# USBHostShield-Rev2.net
KiCad netlist of a schematic drawn in EAGLE
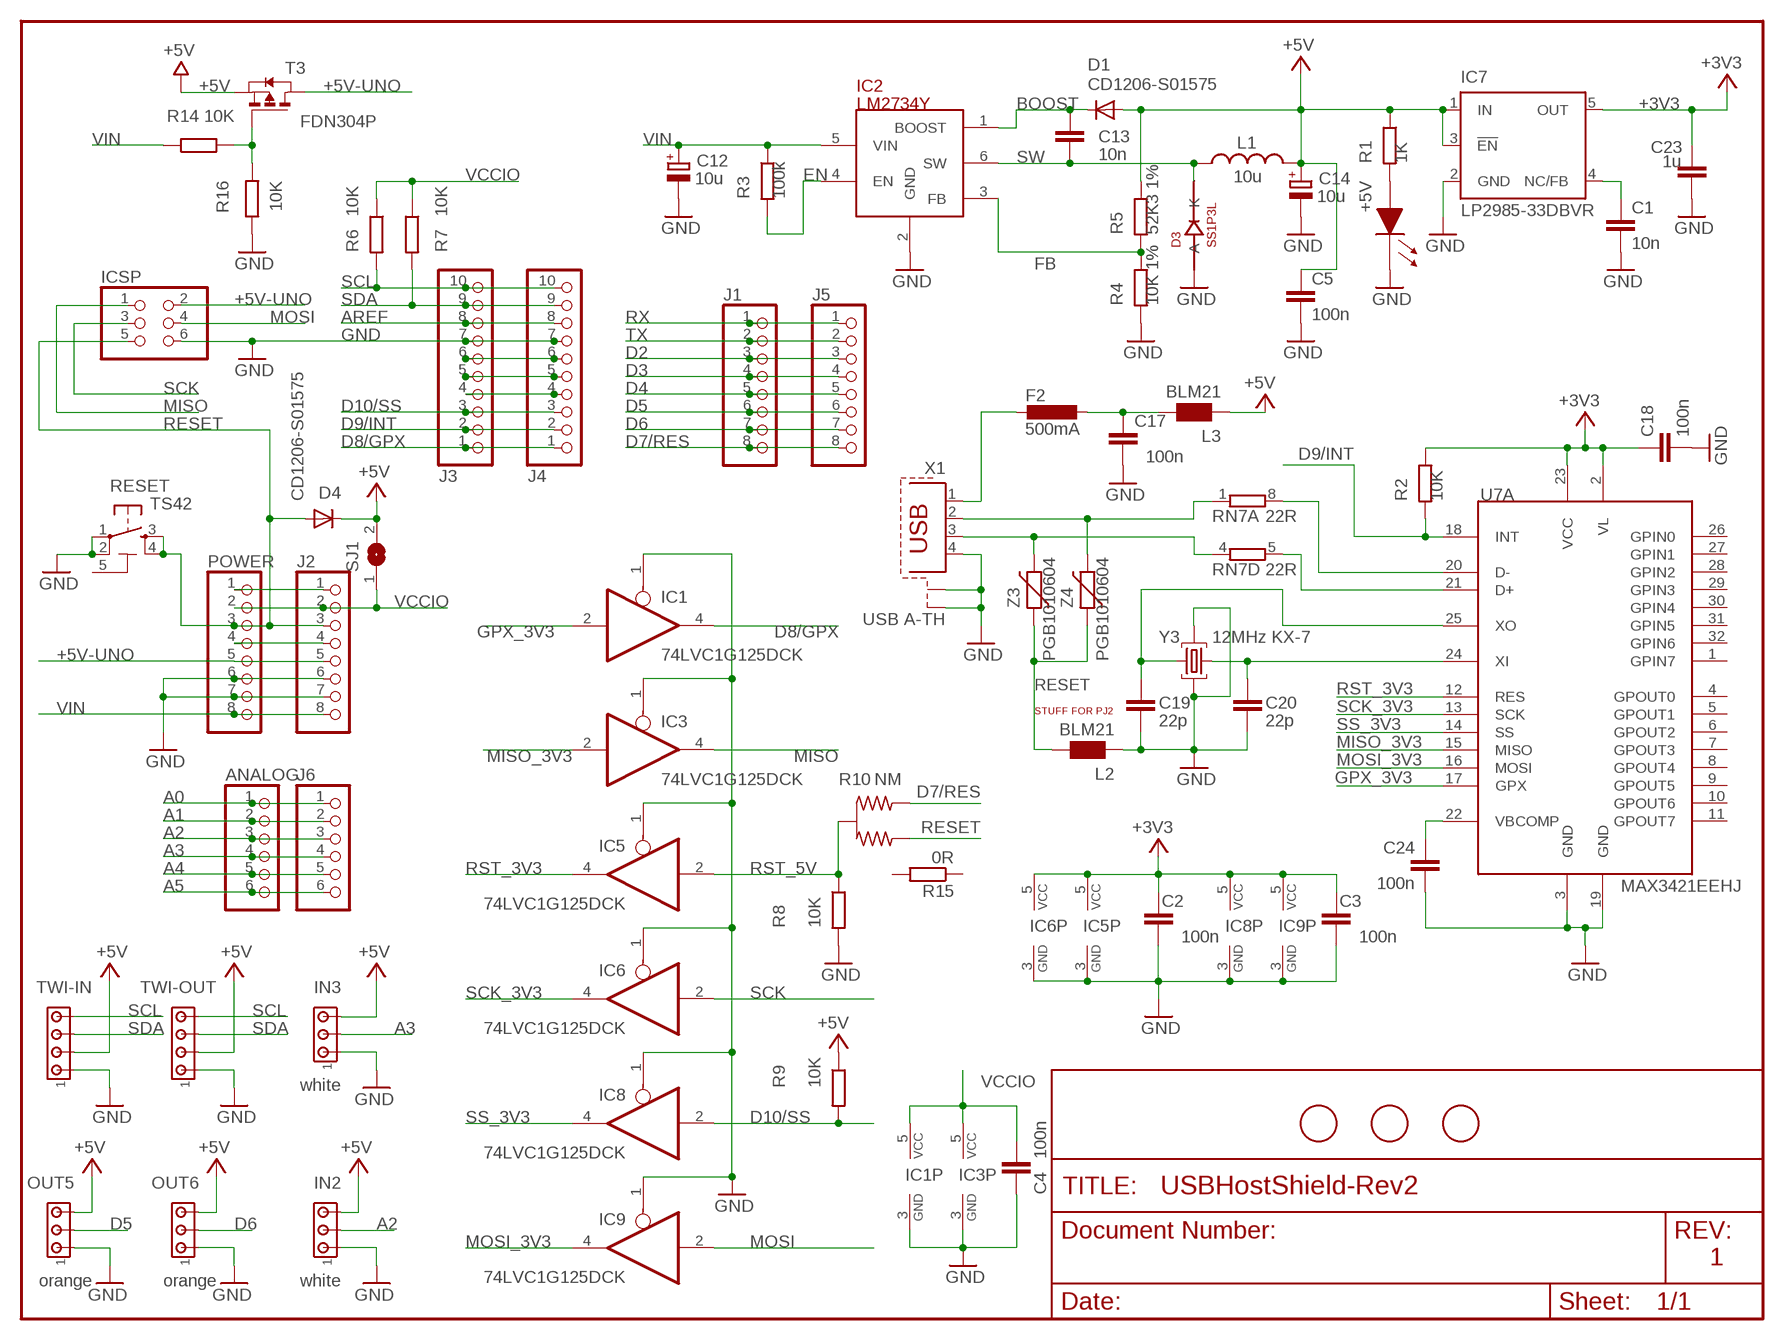
[diagram p0: schematic, sheet 1]

(export (version "E")
  (design (tool "Eeschema 10.0.6"))
  (components
    (comp (ref "+5V")
      (value "MYSMD_LED0805")
      (footprint "eagle-import:SMD_LED0805")
      (libsource (lib "eagle-import") (part "MYSMD_LED0805"))
    )
    (comp (ref "ANALOG")
      (value "PINHD-1X6TH")
      (footprint "eagle-import:1X06-TH")
      (libsource (lib "eagle-import") (part "PINHD-1X6TH"))
    )
    (comp (ref "C1")
      (value "10n")
      (footprint "eagle-import:C0603-ROUND")
      (libsource (lib "eagle-import") (part "C-EUC0603"))
    )
    (comp (ref "C2")
      (value "100n")
      (footprint "eagle-import:C0603-ROUND")
      (libsource (lib "eagle-import") (part "C-EU0603-RND"))
    )
    (comp (ref "C3")
      (value "100n")
      (footprint "eagle-import:C0603-ROUND")
      (libsource (lib "eagle-import") (part "C-EU0603-RND"))
    )
    (comp (ref "C4")
      (value "100n")
      (footprint "eagle-import:C0603-ROUND")
      (libsource (lib "eagle-import") (part "C-EU0603-RND"))
    )
    (comp (ref "C5")
      (value "100n")
      (footprint "eagle-import:C0603-ROUND")
      (libsource (lib "eagle-import") (part "C-EU0603-RND"))
    )
    (comp (ref "C12")
      (value "10u")
      (footprint "eagle-import:SMC_B")
      (libsource (lib "eagle-import") (part "CPOL-EUSMCB"))
    )
    (comp (ref "C13")
      (value "10n")
      (footprint "eagle-import:C0603-ROUND")
      (libsource (lib "eagle-import") (part "C-EUC0603"))
    )
    (comp (ref "C14")
      (value "10u")
      (footprint "eagle-import:SMC_B")
      (libsource (lib "eagle-import") (part "CPOL-EUSMCB"))
    )
    (comp (ref "C17")
      (value "100n")
      (footprint "eagle-import:C0603-ROUND")
      (libsource (lib "eagle-import") (part "C-EU0603-RND"))
    )
    (comp (ref "C18")
      (value "100n")
      (footprint "eagle-import:C0603-ROUND")
      (libsource (lib "eagle-import") (part "C-EU0603-RND"))
    )
    (comp (ref "C19")
      (value "22p")
      (footprint "eagle-import:C0603-ROUND")
      (libsource (lib "eagle-import") (part "C-EU0603-RND"))
    )
    (comp (ref "C20")
      (value "22p")
      (footprint "eagle-import:C0603-ROUND")
      (libsource (lib "eagle-import") (part "C-EU0603-RND"))
    )
    (comp (ref "C23")
      (value "1u")
      (footprint "eagle-import:C0603-ROUND")
      (libsource (lib "eagle-import") (part "C-EU0603-RND"))
    )
    (comp (ref "C24")
      (value "100n")
      (footprint "eagle-import:C0603-ROUND")
      (libsource (lib "eagle-import") (part "C-EU0603-RND"))
    )
    (comp (ref "D1")
      (value "CD1206-S01575")
      (footprint "eagle-import:MINIMELF")
      (libsource (lib "eagle-import") (part "DIODE-MINIMELF"))
    )
    (comp (ref "D3")
      (value "SS1P3L")
      (footprint "eagle-import:DO220AAL")
      (libsource (lib "eagle-import") (part "SS1P3L"))
    )
    (comp (ref "D4")
      (value "CD1206-S01575")
      (footprint "eagle-import:MINIMELF")
      (libsource (lib "eagle-import") (part "DIODE-MINIMELF"))
    )
    (comp (ref "F2")
      (value "500mA")
      (footprint "eagle-import:L1812")
      (libsource (lib "eagle-import") (part "L-EUL1812"))
    )
    (comp (ref "IC1")
      (value "74LVC1G125DCK")
      (footprint "eagle-import:SC70-5")
      (libsource (lib "eagle-import") (part "741G125DCKLVC"))
    )
    (comp (ref "IC2")
      (value "LM2734Y")
      (footprint "eagle-import:SOT23-6")
      (libsource (lib "eagle-import") (part "LM2736Y"))
    )
    (comp (ref "IC3")
      (value "74LVC1G125DCK")
      (footprint "eagle-import:SC70-5")
      (libsource (lib "eagle-import") (part "741G125DCKLVC"))
    )
    (comp (ref "IC5")
      (value "74LVC1G125DCK")
      (footprint "eagle-import:SC70-5")
      (libsource (lib "eagle-import") (part "741G125DCKLVC"))
    )
    (comp (ref "IC6")
      (value "74LVC1G125DCK")
      (footprint "eagle-import:SC70-5")
      (libsource (lib "eagle-import") (part "741G125DCKLVC"))
    )
    (comp (ref "IC7")
      (value "LP2985-33DBVR")
      (footprint "eagle-import:SOT23-DBV")
      (libsource (lib "eagle-import") (part "TPS77033"))
    )
    (comp (ref "IC8")
      (value "74LVC1G125DCK")
      (footprint "eagle-import:SC70-5")
      (libsource (lib "eagle-import") (part "741G125DCKLVC"))
    )
    (comp (ref "IC9")
      (value "74LVC1G125DCK")
      (footprint "eagle-import:SC70-5")
      (libsource (lib "eagle-import") (part "741G125DCKLVC"))
    )
    (comp (ref "ICSP")
      (value "PINHD-2X3")
      (footprint "eagle-import:2X03")
      (libsource (lib "eagle-import") (part "PINHD-2X3"))
    )
    (comp (ref "IN2")
      (value "white")
      (footprint "eagle-import:10X03MTA")
      (fields (field (name "PART_NUMBER") "LHA-03-TS"))
      (libsource (lib "eagle-import") (part "0141_LHA-03-TS"))
    )
    (comp (ref "IN3")
      (value "white")
      (footprint "eagle-import:10X03MTA")
      (fields (field (name "PART_NUMBER") "LHA-03-TS"))
      (libsource (lib "eagle-import") (part "0141_LHA-03-TS"))
    )
    (comp (ref "J1")
      (value "PINHD-1X8TH")
      (footprint "eagle-import:1X08-TH")
      (libsource (lib "eagle-import") (part "PINHD-1X8TH"))
    )
    (comp (ref "J2")
      (value "PINHD-1X8TH")
      (footprint "eagle-import:1X08-TH")
      (libsource (lib "eagle-import") (part "PINHD-1X8TH"))
    )
    (comp (ref "J3")
      (value "PINHD-1X10TH")
      (footprint "eagle-import:1X10-TH")
      (libsource (lib "eagle-import") (part "PINHD-1X10TH"))
    )
    (comp (ref "J4")
      (value "PINHD-1X10TH")
      (footprint "eagle-import:1X10-TH")
      (libsource (lib "eagle-import") (part "PINHD-1X10TH"))
    )
    (comp (ref "J5")
      (value "PINHD-1X8TH")
      (footprint "eagle-import:1X08-TH")
      (libsource (lib "eagle-import") (part "PINHD-1X8TH"))
    )
    (comp (ref "J6")
      (value "PINHD-1X6TH")
      (footprint "eagle-import:1X06-TH")
      (libsource (lib "eagle-import") (part "PINHD-1X6TH"))
    )
    (comp (ref "L1")
      (value "10u")
      (footprint "eagle-import:SRR0604")
      (libsource (lib "eagle-import") (part "L-USSRR0604"))
    )
    (comp (ref "L2")
      (value "BLM21")
      (footprint "eagle-import:0805")
      (libsource (lib "eagle-import") (part "WE-CBF_0805"))
    )
    (comp (ref "L3")
      (value "BLM21")
      (footprint "eagle-import:0805")
      (libsource (lib "eagle-import") (part "WE-CBF_0805"))
    )
    (comp (ref "OUT5")
      (value "orange")
      (footprint "eagle-import:10X03MTA")
      (fields (field (name "PART_NUMBER") "LHA-03-TS-P1585C"))
      (libsource (lib "eagle-import") (part "0481_LHA-03-TS-P1585C"))
    )
    (comp (ref "OUT6")
      (value "orange")
      (footprint "eagle-import:10X03MTA")
      (fields (field (name "PART_NUMBER") "LHA-03-TS-P1585C"))
      (libsource (lib "eagle-import") (part "0481_LHA-03-TS-P1585C"))
    )
    (comp (ref "POWER")
      (value "PINHD-1X8TH")
      (footprint "eagle-import:1X08-TH")
      (libsource (lib "eagle-import") (part "PINHD-1X8TH"))
    )
    (comp (ref "R1")
      (value "1K")
      (footprint "eagle-import:R0603-ROUND")
      (libsource (lib "eagle-import") (part "R-EU_0603-RND"))
    )
    (comp (ref "R2")
      (value "10K")
      (footprint "eagle-import:R0603-ROUND")
      (libsource (lib "eagle-import") (part "R-EU_0603-RND"))
    )
    (comp (ref "R3")
      (value "100k")
      (footprint "eagle-import:R0603-ROUND")
      (libsource (lib "eagle-import") (part "R-EU_0603-RND"))
    )
    (comp (ref "R4")
      (value "10K 1%")
      (footprint "eagle-import:R0603-ROUND")
      (libsource (lib "eagle-import") (part "R-EU_0603-RND"))
    )
    (comp (ref "R5")
      (value "52K3 1%")
      (footprint "eagle-import:R0603-ROUND")
      (libsource (lib "eagle-import") (part "R-EU_0603-RND"))
    )
    (comp (ref "R6")
      (value "10K")
      (footprint "eagle-import:R0603-ROUND")
      (libsource (lib "eagle-import") (part "R-EU_0603-RND"))
    )
    (comp (ref "R7")
      (value "10K")
      (footprint "eagle-import:R0603-ROUND")
      (libsource (lib "eagle-import") (part "R-EU_0603-RND"))
    )
    (comp (ref "R8")
      (value "10K")
      (footprint "eagle-import:R0603-ROUND")
      (libsource (lib "eagle-import") (part "R-EU_0603-RND"))
    )
    (comp (ref "R9")
      (value "10K")
      (footprint "eagle-import:R0603-ROUND")
      (libsource (lib "eagle-import") (part "R-EU_0603-RND"))
    )
    (comp (ref "R10")
      (value "NM")
      (footprint "eagle-import:J0402")
      (libsource (lib "eagle-import") (part "J0402"))
    )
    (comp (ref "R14")
      (value "10K")
      (footprint "eagle-import:R0603-ROUND")
      (libsource (lib "eagle-import") (part "R-EU_0603-RND"))
    )
    (comp (ref "R15")
      (value "0R")
      (footprint "eagle-import:R0402")
      (libsource (lib "eagle-import") (part "R-EU_R0402"))
    )
    (comp (ref "R16")
      (value "10K")
      (footprint "eagle-import:R0603-ROUND")
      (libsource (lib "eagle-import") (part "R-EU_0603-RND"))
    )
    (comp (ref "RESET")
      (value "TS42")
      (footprint "eagle-import:TS42")
      (libsource (lib "eagle-import") (part "TS42"))
    )
    (comp (ref "RN7")
      (value "22R")
      (footprint "eagle-import:CAY16")
      (libsource (lib "eagle-import") (part "4R-NCAY16"))
    )
    (comp (ref "SJ1") (value "SJ") (footprint "eagle-import:SJ") (libsource (lib "eagle-import") (part "SJ")))
    (comp (ref "T3")
      (value "FDN304P")
      (footprint "eagle-import:SOT-23")
      (libsource (lib "eagle-import") (part "PMOSSOT23"))
    )
    (comp (ref "TWI-IN")
      (value "0205_LHA-04-TS__4X1_VERTICALE_BIANCO_P_2,54")
      (footprint "eagle-import:10X04MTA")
      (fields (field (name "PART_NUMBER") "LHA-04-TS__4x1_Verticale_Bianco_p_2,54"))
      (libsource (lib "eagle-import") (part "0205_LHA-04-TS__4X1_VERTICALE_BIANCO_P_2,54"))
    )
    (comp (ref "TWI-OUT")
      (value "0205_LHA-04-TS__4X1_VERTICALE_BIANCO_P_2,54")
      (footprint "eagle-import:10X04MTA")
      (fields (field (name "PART_NUMBER") "LHA-04-TS__4x1_Verticale_Bianco_p_2,54"))
      (libsource (lib "eagle-import") (part "0205_LHA-04-TS__4X1_VERTICALE_BIANCO_P_2,54"))
    )
    (comp (ref "U$1")
      (value "FIDUCIALMOUNT")
      (footprint "eagle-import:FIDUCIA-MOUNT")
      (libsource (lib "eagle-import") (part "FIDUCIALMOUNT"))
    )
    (comp (ref "U$3")
      (value "FIDUCIALMOUNT")
      (footprint "eagle-import:FIDUCIA-MOUNT")
      (libsource (lib "eagle-import") (part "FIDUCIALMOUNT"))
    )
    (comp (ref "U$6")
      (value "FIDUCIALMOUNT")
      (footprint "eagle-import:FIDUCIA-MOUNT")
      (libsource (lib "eagle-import") (part "FIDUCIALMOUNT"))
    )
    (comp (ref "U7A")
      (value "MAX3421EEHJ")
      (footprint "eagle-import:TQFP32-05")
      (libsource (lib "eagle-import") (part "MAX3421EEHJ"))
    )
    (comp (ref "X1")
      (value "USB A-TH")
      (footprint "eagle-import:PN87520-S")
      (libsource (lib "eagle-import") (part "PN87520-S"))
    )
    (comp (ref "Y3")
      (value "12MHz KX-7")
      (footprint "eagle-import:CRYSTAL-3.2-2.5")
      (libsource (lib "eagle-import") (part "CRYSTAL-3.2-2.5"))
    )
    (comp (ref "Z3")
      (value "PGB1010604")
      (footprint "eagle-import:CT_CN0603")
      (libsource (lib "eagle-import") (part "VARISTORCN0603"))
    )
    (comp (ref "Z4")
      (value "PGB1010604")
      (footprint "eagle-import:CT_CN0603")
      (libsource (lib "eagle-import") (part "VARISTORCN0603"))
    )
  )
  (nets
    (net (code "1") (name "+3V3") (class "Default")
      (node (ref "C18") (pin "1") (pinfunction "1_1") (pintype "passive"))
      (node (ref "C2") (pin "1") (pinfunction "1_1") (pintype "passive"))
      (node (ref "C23") (pin "2") (pinfunction "2_2") (pintype "passive"))
      (node (ref "C3") (pin "1") (pinfunction "1_1") (pintype "passive"))
      (node (ref "IC5") (pin "5") (pinfunction "VCC_5") (pintype "power_in"))
      (node (ref "IC6") (pin "5") (pinfunction "VCC_5") (pintype "power_in"))
      (node (ref "IC7") (pin "5") (pinfunction "OUT_5") (pintype "passive"))
      (node (ref "IC8") (pin "5") (pinfunction "VCC_5") (pintype "power_in"))
      (node (ref "IC9") (pin "5") (pinfunction "VCC_5") (pintype "power_in"))
      (node (ref "R2") (pin "1") (pinfunction "1_1") (pintype "passive"))
      (node (ref "U7A") (pin "2") (pinfunction "VL_2") (pintype "bidirectional"))
      (node (ref "U7A") (pin "23") (pinfunction "VCC_23") (pintype "bidirectional"))
    )
    (net (code "2") (name "+5V") (class "Default")
      (node (ref "C14") (pin "+") (pinfunction "+_+") (pintype "passive"))
      (node (ref "C5") (pin "1") (pinfunction "1_1") (pintype "passive"))
      (node (ref "D1") (pin "A") (pinfunction "A_A") (pintype "passive"))
      (node (ref "D4") (pin "C") (pinfunction "C_C") (pintype "passive"))
      (node (ref "IC7") (pin "1") (pinfunction "IN_1") (pintype "input"))
      (node (ref "IC7") (pin "3") (pinfunction "~{EN}_3") (pintype "input"))
      (node (ref "IN2") (pin "3") (pinfunction "3_3") (pintype "passive"))
      (node (ref "IN3") (pin "3") (pinfunction "3_3") (pintype "passive"))
      (node (ref "L1") (pin "P$2") (pinfunction "2_P$2") (pintype "passive"))
      (node (ref "L3") (pin "1") (pinfunction "1_1") (pintype "passive"))
      (node (ref "OUT5") (pin "3") (pinfunction "3_3") (pintype "passive"))
      (node (ref "OUT6") (pin "3") (pinfunction "3_3") (pintype "passive"))
      (node (ref "R1") (pin "1") (pinfunction "1_1") (pintype "passive"))
      (node (ref "R5") (pin "1") (pinfunction "1_1") (pintype "passive"))
      (node (ref "R9") (pin "1") (pinfunction "1_1") (pintype "passive"))
      (node (ref "SJ1") (pin "2") (pinfunction "2_2") (pintype "passive"))
      (node (ref "T3") (pin "2") (pinfunction "S_2") (pintype "passive"))
      (node (ref "TWI-IN") (pin "2") (pinfunction "2_2") (pintype "passive"))
      (node (ref "TWI-OUT") (pin "2") (pinfunction "2_2") (pintype "passive"))
    )
    (net (code "3") (name "/+5V-UNO") (class "Default")
      (node (ref "ICSP") (pin "2") (pinfunction "2_2") (pintype "passive"))
      (node (ref "J2") (pin "5") (pinfunction "5_5") (pintype "passive"))
      (node (ref "POWER") (pin "5") (pinfunction "5_5") (pintype "passive"))
      (node (ref "T3") (pin "1") (pinfunction "D_1") (pintype "passive"))
    )
    (net (code "4") (name "/5-GND") (class "Default")
      (node (ref "RESET") (pin "5") (pinfunction "5-GND_5") (pintype "power_in"))
    )
    (net (code "5") (name "/A0") (class "Default")
      (node (ref "ANALOG") (pin "1") (pinfunction "1_1") (pintype "passive"))
      (node (ref "J6") (pin "1") (pinfunction "1_1") (pintype "passive"))
    )
    (net (code "6") (name "/A1") (class "Default")
      (node (ref "ANALOG") (pin "2") (pinfunction "2_2") (pintype "passive"))
      (node (ref "J6") (pin "2") (pinfunction "2_2") (pintype "passive"))
    )
    (net (code "7") (name "/A2") (class "Default")
      (node (ref "ANALOG") (pin "3") (pinfunction "3_3") (pintype "passive"))
      (node (ref "IN2") (pin "2") (pinfunction "2_2") (pintype "passive"))
      (node (ref "J6") (pin "3") (pinfunction "3_3") (pintype "passive"))
    )
    (net (code "8") (name "/A3") (class "Default")
      (node (ref "ANALOG") (pin "4") (pinfunction "4_4") (pintype "passive"))
      (node (ref "IN3") (pin "2") (pinfunction "2_2") (pintype "passive"))
      (node (ref "J6") (pin "4") (pinfunction "4_4") (pintype "passive"))
    )
    (net (code "9") (name "/A4") (class "Default")
      (node (ref "ANALOG") (pin "5") (pinfunction "5_5") (pintype "passive"))
      (node (ref "J6") (pin "5") (pinfunction "5_5") (pintype "passive"))
    )
    (net (code "10") (name "/A5") (class "Default")
      (node (ref "ANALOG") (pin "6") (pinfunction "6_6") (pintype "passive"))
      (node (ref "J6") (pin "6") (pinfunction "6_6") (pintype "passive"))
    )
    (net (code "11") (name "/AREF") (class "Default")
      (node (ref "J3") (pin "8") (pinfunction "8_8") (pintype "passive"))
      (node (ref "J4") (pin "8") (pinfunction "8_8") (pintype "passive"))
    )
    (net (code "12") (name "/BOOST") (class "Default")
      (node (ref "C13") (pin "1") (pinfunction "1_1") (pintype "passive"))
      (node (ref "D1") (pin "C") (pinfunction "C_C") (pintype "passive"))
      (node (ref "IC2") (pin "1") (pinfunction "BOOST_1") (pintype "input"))
    )
    (net (code "13") (name "/D2") (class "Default")
      (node (ref "J1") (pin "3") (pinfunction "3_3") (pintype "passive"))
      (node (ref "J5") (pin "3") (pinfunction "3_3") (pintype "passive"))
    )
    (net (code "14") (name "/D3") (class "Default")
      (node (ref "J1") (pin "4") (pinfunction "4_4") (pintype "passive"))
      (node (ref "J5") (pin "4") (pinfunction "4_4") (pintype "passive"))
    )
    (net (code "15") (name "/D4") (class "Default")
      (node (ref "J1") (pin "5") (pinfunction "5_5") (pintype "passive"))
      (node (ref "J5") (pin "5") (pinfunction "5_5") (pintype "passive"))
    )
    (net (code "16") (name "/D5") (class "Default")
      (node (ref "J1") (pin "6") (pinfunction "6_6") (pintype "passive"))
      (node (ref "J5") (pin "6") (pinfunction "6_6") (pintype "passive"))
      (node (ref "OUT5") (pin "2") (pinfunction "2_2") (pintype "passive"))
    )
    (net (code "17") (name "/D6") (class "Default")
      (node (ref "J1") (pin "7") (pinfunction "7_7") (pintype "passive"))
      (node (ref "J5") (pin "7") (pinfunction "7_7") (pintype "passive"))
      (node (ref "OUT6") (pin "2") (pinfunction "2_2") (pintype "passive"))
    )
    (net (code "18") (name "/D7{slash}RES") (class "Default")
      (node (ref "J1") (pin "8") (pinfunction "8_8") (pintype "passive"))
      (node (ref "J5") (pin "8") (pinfunction "8_8") (pintype "passive"))
      (node (ref "R10") (pin "1") (pinfunction "1_1") (pintype "passive"))
    )
    (net (code "19") (name "/D8{slash}GPX") (class "Default")
      (node (ref "IC1") (pin "4") (pinfunction "O_4") (pintype "tri_state"))
      (node (ref "J3") (pin "1") (pinfunction "1_1") (pintype "passive"))
      (node (ref "J4") (pin "1") (pinfunction "1_1") (pintype "passive"))
    )
    (net (code "20") (name "/D9{slash}INT") (class "Default")
      (node (ref "J3") (pin "2") (pinfunction "2_2") (pintype "passive"))
      (node (ref "J4") (pin "2") (pinfunction "2_2") (pintype "passive"))
      (node (ref "R2") (pin "2") (pinfunction "2_2") (pintype "passive"))
      (node (ref "U7A") (pin "18") (pinfunction "INT_18") (pintype "bidirectional"))
    )
    (net (code "21") (name "/D10{slash}SS") (class "Default")
      (node (ref "IC8") (pin "2") (pinfunction "I_2") (pintype "input"))
      (node (ref "J3") (pin "3") (pinfunction "3_3") (pintype "passive"))
      (node (ref "J4") (pin "3") (pinfunction "3_3") (pintype "passive"))
      (node (ref "R9") (pin "2") (pinfunction "2_2") (pintype "passive"))
    )
    (net (code "22") (name "/EN") (class "Default")
      (node (ref "IC2") (pin "4") (pinfunction "EN_4") (pintype "input"))
      (node (ref "R3") (pin "2") (pinfunction "2_2") (pintype "passive"))
    )
    (net (code "23") (name "/FB") (class "Default")
      (node (ref "IC2") (pin "3") (pinfunction "FB_3") (pintype "input"))
      (node (ref "R4") (pin "1") (pinfunction "1_1") (pintype "passive"))
      (node (ref "R5") (pin "2") (pinfunction "2_2") (pintype "passive"))
    )
    (net (code "24") (name "/GPX_3V3") (class "Default")
      (node (ref "IC1") (pin "2") (pinfunction "I_2") (pintype "input"))
      (node (ref "U7A") (pin "17") (pinfunction "GPX_17") (pintype "bidirectional"))
    )
    (net (code "25") (name "/MISO") (class "Default")
      (node (ref "IC3") (pin "4") (pinfunction "O_4") (pintype "tri_state"))
      (node (ref "ICSP") (pin "1") (pinfunction "1_1") (pintype "passive"))
    )
    (net (code "26") (name "/MISO_3V3") (class "Default")
      (node (ref "IC3") (pin "2") (pinfunction "I_2") (pintype "input"))
      (node (ref "U7A") (pin "15") (pinfunction "MISO_15") (pintype "bidirectional"))
    )
    (net (code "27") (name "/MOSI") (class "Default")
      (node (ref "IC9") (pin "2") (pinfunction "I_2") (pintype "input"))
      (node (ref "ICSP") (pin "4") (pinfunction "4_4") (pintype "passive"))
    )
    (net (code "28") (name "/MOSI_3V3") (class "Default")
      (node (ref "IC9") (pin "4") (pinfunction "O_4") (pintype "tri_state"))
      (node (ref "U7A") (pin "16") (pinfunction "MOSI_16") (pintype "bidirectional"))
    )
    (net (code "29") (name "/RESET") (class "Default")
      (node (ref "D4") (pin "A") (pinfunction "A_A") (pintype "passive"))
      (node (ref "ICSP") (pin "5") (pinfunction "5_5") (pintype "passive"))
      (node (ref "J2") (pin "3") (pinfunction "3_3") (pintype "passive"))
      (node (ref "POWER") (pin "3") (pinfunction "3_3") (pintype "passive"))
      (node (ref "R10") (pin "3") (pinfunction "2_3") (pintype "passive"))
      (node (ref "RESET") (pin "3") (pinfunction "3_3") (pintype "passive"))
      (node (ref "RESET") (pin "4") (pinfunction "4_4") (pintype "passive"))
    )
    (net (code "30") (name "/RST_3V3") (class "Default")
      (node (ref "IC5") (pin "4") (pinfunction "O_4") (pintype "tri_state"))
      (node (ref "U7A") (pin "12") (pinfunction "RES_12") (pintype "bidirectional"))
    )
    (net (code "31") (name "/RST_5V") (class "Default")
      (node (ref "IC5") (pin "2") (pinfunction "I_2") (pintype "input"))
      (node (ref "R10") (pin "2") (pinfunction "C_2") (pintype "passive"))
      (node (ref "R8") (pin "1") (pinfunction "1_1") (pintype "passive"))
    )
    (net (code "32") (name "/RX") (class "Default")
      (node (ref "J1") (pin "1") (pinfunction "1_1") (pintype "passive"))
      (node (ref "J5") (pin "1") (pinfunction "1_1") (pintype "passive"))
    )
    (net (code "33") (name "/SCK") (class "Default")
      (node (ref "IC6") (pin "2") (pinfunction "I_2") (pintype "input"))
      (node (ref "ICSP") (pin "3") (pinfunction "3_3") (pintype "passive"))
    )
    (net (code "34") (name "/SCK_3V3") (class "Default")
      (node (ref "IC6") (pin "4") (pinfunction "O_4") (pintype "tri_state"))
      (node (ref "U7A") (pin "13") (pinfunction "SCK_13") (pintype "bidirectional"))
    )
    (net (code "35") (name "/SCL") (class "Default")
      (node (ref "J3") (pin "10") (pinfunction "10_10") (pintype "passive"))
      (node (ref "J4") (pin "10") (pinfunction "10_10") (pintype "passive"))
      (node (ref "R6") (pin "2") (pinfunction "2_2") (pintype "passive"))
      (node (ref "TWI-IN") (pin "4") (pinfunction "4_4") (pintype "passive"))
      (node (ref "TWI-OUT") (pin "4") (pinfunction "4_4") (pintype "passive"))
    )
    (net (code "36") (name "/SDA") (class "Default")
      (node (ref "J3") (pin "9") (pinfunction "9_9") (pintype "passive"))
      (node (ref "J4") (pin "9") (pinfunction "9_9") (pintype "passive"))
      (node (ref "R7") (pin "2") (pinfunction "2_2") (pintype "passive"))
      (node (ref "TWI-IN") (pin "3") (pinfunction "3_3") (pintype "passive"))
      (node (ref "TWI-OUT") (pin "3") (pinfunction "3_3") (pintype "passive"))
    )
    (net (code "37") (name "/SS_3V3") (class "Default")
      (node (ref "IC8") (pin "4") (pinfunction "O_4") (pintype "tri_state"))
      (node (ref "U7A") (pin "14") (pinfunction "SS_14") (pintype "bidirectional"))
    )
    (net (code "38") (name "/SW") (class "Default")
      (node (ref "C13") (pin "2") (pinfunction "2_2") (pintype "passive"))
      (node (ref "D3") (pin "P$1") (pinfunction "K_P$1") (pintype "bidirectional"))
      (node (ref "IC2") (pin "6") (pinfunction "SW_6") (pintype "output"))
      (node (ref "L1") (pin "P$1") (pinfunction "1_P$1") (pintype "passive"))
    )
    (net (code "39") (name "/TX") (class "Default")
      (node (ref "J1") (pin "2") (pinfunction "2_2") (pintype "passive"))
      (node (ref "J5") (pin "2") (pinfunction "2_2") (pintype "passive"))
    )
    (net (code "40") (name "/VCCIO") (class "Default")
      (node (ref "C4") (pin "1") (pinfunction "1_1") (pintype "passive"))
      (node (ref "IC1") (pin "5") (pinfunction "VCC_5") (pintype "power_in"))
      (node (ref "IC3") (pin "5") (pinfunction "VCC_5") (pintype "power_in"))
      (node (ref "J2") (pin "2") (pinfunction "2_2") (pintype "passive"))
      (node (ref "POWER") (pin "2") (pinfunction "2_2") (pintype "passive"))
      (node (ref "R6") (pin "1") (pinfunction "1_1") (pintype "passive"))
      (node (ref "R7") (pin "1") (pinfunction "1_1") (pintype "passive"))
      (node (ref "SJ1") (pin "1") (pinfunction "1_1") (pintype "passive"))
    )
    (net (code "41") (name "/VIN") (class "Default")
      (node (ref "C12") (pin "+") (pinfunction "+_+") (pintype "passive"))
      (node (ref "IC2") (pin "5") (pinfunction "VIN_5") (pintype "input"))
      (node (ref "J2") (pin "8") (pinfunction "8_8") (pintype "passive"))
      (node (ref "POWER") (pin "8") (pinfunction "8_8") (pintype "passive"))
      (node (ref "R14") (pin "1") (pinfunction "1_1") (pintype "passive"))
      (node (ref "R3") (pin "1") (pinfunction "1_1") (pintype "passive"))
    )
    (net (code "42") (name "GND") (class "Default")
      (node (ref "+5V") (pin "1") (pinfunction "CA_1") (pintype "passive"))
      (node (ref "C1") (pin "2") (pinfunction "2_2") (pintype "passive"))
      (node (ref "C12") (pin "-") (pinfunction "-_-") (pintype "passive"))
      (node (ref "C14") (pin "-") (pinfunction "-_-") (pintype "passive"))
      (node (ref "C17") (pin "2") (pinfunction "2_2") (pintype "passive"))
      (node (ref "C18") (pin "2") (pinfunction "2_2") (pintype "passive"))
      (node (ref "C19") (pin "1") (pinfunction "1_1") (pintype "passive"))
      (node (ref "C2") (pin "2") (pinfunction "2_2") (pintype "passive"))
      (node (ref "C20") (pin "1") (pinfunction "1_1") (pintype "passive"))
      (node (ref "C23") (pin "1") (pinfunction "1_1") (pintype "passive"))
      (node (ref "C24") (pin "2") (pinfunction "2_2") (pintype "passive"))
      (node (ref "C3") (pin "2") (pinfunction "2_2") (pintype "passive"))
      (node (ref "C4") (pin "2") (pinfunction "2_2") (pintype "passive"))
      (node (ref "C5") (pin "2") (pinfunction "2_2") (pintype "passive"))
      (node (ref "D3") (pin "P$2") (pinfunction "A_P$2") (pintype "bidirectional"))
      (node (ref "IC1") (pin "1") (pinfunction "OE_1") (pintype "input"))
      (node (ref "IC1") (pin "3") (pinfunction "GND_3") (pintype "power_in"))
      (node (ref "IC2") (pin "2") (pinfunction "GND_2") (pintype "power_in"))
      (node (ref "IC3") (pin "1") (pinfunction "OE_1") (pintype "input"))
      (node (ref "IC3") (pin "3") (pinfunction "GND_3") (pintype "power_in"))
      (node (ref "IC5") (pin "1") (pinfunction "OE_1") (pintype "input"))
      (node (ref "IC5") (pin "3") (pinfunction "GND_3") (pintype "power_in"))
      (node (ref "IC6") (pin "1") (pinfunction "OE_1") (pintype "input"))
      (node (ref "IC6") (pin "3") (pinfunction "GND_3") (pintype "power_in"))
      (node (ref "IC7") (pin "2") (pinfunction "GND_2") (pintype "power_in"))
      (node (ref "IC8") (pin "1") (pinfunction "OE_1") (pintype "input"))
      (node (ref "IC8") (pin "3") (pinfunction "GND_3") (pintype "power_in"))
      (node (ref "IC9") (pin "1") (pinfunction "OE_1") (pintype "input"))
      (node (ref "IC9") (pin "3") (pinfunction "GND_3") (pintype "power_in"))
      (node (ref "ICSP") (pin "6") (pinfunction "6_6") (pintype "passive"))
      (node (ref "IN2") (pin "1") (pinfunction "1_1") (pintype "passive"))
      (node (ref "IN3") (pin "1") (pinfunction "1_1") (pintype "passive"))
      (node (ref "J2") (pin "6") (pinfunction "6_6") (pintype "passive"))
      (node (ref "J2") (pin "7") (pinfunction "7_7") (pintype "passive"))
      (node (ref "J3") (pin "7") (pinfunction "7_7") (pintype "passive"))
      (node (ref "J4") (pin "7") (pinfunction "7_7") (pintype "passive"))
      (node (ref "L2") (pin "1") (pinfunction "1_1") (pintype "passive"))
      (node (ref "OUT5") (pin "1") (pinfunction "1_1") (pintype "passive"))
      (node (ref "OUT6") (pin "1") (pinfunction "1_1") (pintype "passive"))
      (node (ref "POWER") (pin "6") (pinfunction "6_6") (pintype "passive"))
      (node (ref "POWER") (pin "7") (pinfunction "7_7") (pintype "passive"))
      (node (ref "R16") (pin "1") (pinfunction "1_1") (pintype "passive"))
      (node (ref "R4") (pin "2") (pinfunction "2_2") (pintype "passive"))
      (node (ref "R8") (pin "2") (pinfunction "2_2") (pintype "passive"))
      (node (ref "RESET") (pin "1") (pinfunction "1_1") (pintype "passive"))
      (node (ref "RESET") (pin "2") (pinfunction "2_2") (pintype "passive"))
      (node (ref "TWI-IN") (pin "1") (pinfunction "1_1") (pintype "passive"))
      (node (ref "TWI-OUT") (pin "1") (pinfunction "1_1") (pintype "passive"))
      (node (ref "U7A") (pin "19") (pinfunction "GND_19") (pintype "bidirectional"))
      (node (ref "U7A") (pin "3") (pinfunction "GND_3") (pintype "bidirectional"))
      (node (ref "X1") (pin "4") (pinfunction "4_4") (pintype "passive"))
      (node (ref "X1") (pin "S1") (pinfunction "S1_S1") (pintype "passive"))
      (node (ref "X1") (pin "S2") (pinfunction "S2_S2") (pintype "passive"))
      (node (ref "Y3") (pin "2") (pinfunction "GND_2") (pintype "passive"))
      (node (ref "Y3") (pin "4") (pinfunction "GND_4") (pintype "passive"))
    )
    (net (code "43") (name "Net-(+5V-AN)") (class "Default")
      (node (ref "+5V") (pin "2") (pinfunction "AN_2") (pintype "passive"))
      (node (ref "R1") (pin "2") (pinfunction "2_2") (pintype "passive"))
    )
    (net (code "44") (name "Net-(C17-Pad1)") (class "Default")
      (node (ref "C17") (pin "1") (pinfunction "1_1") (pintype "passive"))
      (node (ref "F2") (pin "1") (pinfunction "1_1") (pintype "passive"))
      (node (ref "L3") (pin "2") (pinfunction "2_2") (pintype "passive"))
    )
    (net (code "45") (name "Net-(F2-Pad2)") (class "Default")
      (node (ref "F2") (pin "2") (pinfunction "2_2") (pintype "passive"))
      (node (ref "X1") (pin "1") (pinfunction "1_1") (pintype "passive"))
    )
    (net (code "46") (name "Net-(IC7-NC{slash}FB)") (class "Default")
      (node (ref "C1") (pin "1") (pinfunction "1_1") (pintype "passive"))
      (node (ref "IC7") (pin "4") (pinfunction "NC/FB_4") (pintype "passive"))
    )
    (net (code "47") (name "Net-(J2-Pad1)") (class "Default")
      (node (ref "J2") (pin "1") (pinfunction "1_1") (pintype "passive"))
      (node (ref "POWER") (pin "1") (pinfunction "1_1") (pintype "passive"))
    )
    (net (code "48") (name "Net-(J2-Pad4)") (class "Default")
      (node (ref "J2") (pin "4") (pinfunction "4_4") (pintype "passive"))
      (node (ref "POWER") (pin "4") (pinfunction "4_4") (pintype "passive"))
    )
    (net (code "49") (name "Net-(J3-Pad4)") (class "Default")
      (node (ref "J3") (pin "4") (pinfunction "4_4") (pintype "passive"))
      (node (ref "J4") (pin "4") (pinfunction "4_4") (pintype "passive"))
    )
    (net (code "50") (name "Net-(J3-Pad5)") (class "Default")
      (node (ref "J3") (pin "5") (pinfunction "5_5") (pintype "passive"))
      (node (ref "J4") (pin "5") (pinfunction "5_5") (pintype "passive"))
    )
    (net (code "51") (name "Net-(J3-Pad6)") (class "Default")
      (node (ref "J3") (pin "6") (pinfunction "6_6") (pintype "passive"))
      (node (ref "J4") (pin "6") (pinfunction "6_6") (pintype "passive"))
    )
    (net (code "52") (name "Net-(L2-Pad2)") (class "Default")
      (node (ref "L2") (pin "2") (pinfunction "2_2") (pintype "passive"))
      (node (ref "Z3") (pin "1") (pinfunction "1_1") (pintype "passive"))
      (node (ref "Z4") (pin "1") (pinfunction "1_1") (pintype "passive"))
    )
    (net (code "53") (name "Net-(RN7-Pad1)") (class "Default")
      (node (ref "RN7") (pin "1") (pinfunction "1_1") (pintype "passive"))
      (node (ref "X1") (pin "2") (pinfunction "2_2") (pintype "passive"))
      (node (ref "Z4") (pin "2") (pinfunction "2_2") (pintype "passive"))
    )
    (net (code "54") (name "Net-(RN7A-2)") (class "Default")
      (node (ref "RN7") (pin "8") (pinfunction "2_8") (pintype "passive"))
      (node (ref "U7A") (pin "20") (pinfunction "D-_20") (pintype "bidirectional"))
    )
    (net (code "55") (name "Net-(RN7D-1)") (class "Default")
      (node (ref "RN7") (pin "4") (pinfunction "1_4") (pintype "passive"))
      (node (ref "X1") (pin "3") (pinfunction "3_3") (pintype "passive"))
      (node (ref "Z3") (pin "2") (pinfunction "2_2") (pintype "passive"))
    )
    (net (code "56") (name "Net-(RN7D-2)") (class "Default")
      (node (ref "RN7") (pin "5") (pinfunction "2_5") (pintype "passive"))
      (node (ref "U7A") (pin "21") (pinfunction "D+_21") (pintype "bidirectional"))
    )
    (net (code "57") (name "Net-(T3-G)") (class "Default")
      (node (ref "R14") (pin "2") (pinfunction "2_2") (pintype "passive"))
      (node (ref "R16") (pin "2") (pinfunction "2_2") (pintype "passive"))
      (node (ref "T3") (pin "3") (pinfunction "G_3") (pintype "passive"))
    )
    (net (code "58") (name "Net-(U7A-VBCOMP)") (class "Default")
      (node (ref "C24") (pin "1") (pinfunction "1_1") (pintype "passive"))
      (node (ref "U7A") (pin "22") (pinfunction "VBCOMP_22") (pintype "bidirectional"))
    )
    (net (code "59") (name "Net-(U7A-XI)") (class "Default")
      (node (ref "C20") (pin "2") (pinfunction "2_2") (pintype "passive"))
      (node (ref "U7A") (pin "24") (pinfunction "XI_24") (pintype "bidirectional"))
      (node (ref "Y3") (pin "1") (pinfunction "C1_1") (pintype "passive"))
    )
    (net (code "60") (name "Net-(U7A-XO)") (class "Default")
      (node (ref "C19") (pin "2") (pinfunction "2_2") (pintype "passive"))
      (node (ref "U7A") (pin "25") (pinfunction "XO_25") (pintype "bidirectional"))
      (node (ref "Y3") (pin "3") (pinfunction "C2_3") (pintype "passive"))
    )
    (net (code "61") (name "unconnected-(R15-Pad1)") (class "Default")
      (node (ref "R15") (pin "1") (pinfunction "1_1") (pintype "passive"))
    )
    (net (code "62") (name "unconnected-(R15-Pad2)") (class "Default")
      (node (ref "R15") (pin "2") (pinfunction "2_2") (pintype "passive"))
    )
    (net (code "63") (name "unconnected-(U7A-GPIN0-Pad26)") (class "Default")
      (node (ref "U7A") (pin "26") (pinfunction "GPIN0_26") (pintype "bidirectional"))
    )
    (net (code "64") (name "unconnected-(U7A-GPIN1-Pad27)") (class "Default")
      (node (ref "U7A") (pin "27") (pinfunction "GPIN1_27") (pintype "bidirectional"))
    )
    (net (code "65") (name "unconnected-(U7A-GPIN2-Pad28)") (class "Default")
      (node (ref "U7A") (pin "28") (pinfunction "GPIN2_28") (pintype "bidirectional"))
    )
    (net (code "66") (name "unconnected-(U7A-GPIN3-Pad29)") (class "Default")
      (node (ref "U7A") (pin "29") (pinfunction "GPIN3_29") (pintype "bidirectional"))
    )
    (net (code "67") (name "unconnected-(U7A-GPIN4-Pad30)") (class "Default")
      (node (ref "U7A") (pin "30") (pinfunction "GPIN4_30") (pintype "bidirectional"))
    )
    (net (code "68") (name "unconnected-(U7A-GPIN5-Pad31)") (class "Default")
      (node (ref "U7A") (pin "31") (pinfunction "GPIN5_31") (pintype "bidirectional"))
    )
    (net (code "69") (name "unconnected-(U7A-GPIN6-Pad32)") (class "Default")
      (node (ref "U7A") (pin "32") (pinfunction "GPIN6_32") (pintype "bidirectional"))
    )
    (net (code "70") (name "unconnected-(U7A-GPIN7-Pad1)") (class "Default")
      (node (ref "U7A") (pin "1") (pinfunction "GPIN7_1") (pintype "bidirectional"))
    )
    (net (code "71") (name "unconnected-(U7A-GPOUT0-Pad4)") (class "Default")
      (node (ref "U7A") (pin "4") (pinfunction "GPOUT0_4") (pintype "bidirectional"))
    )
    (net (code "72") (name "unconnected-(U7A-GPOUT1-Pad5)") (class "Default")
      (node (ref "U7A") (pin "5") (pinfunction "GPOUT1_5") (pintype "bidirectional"))
    )
    (net (code "73") (name "unconnected-(U7A-GPOUT2-Pad6)") (class "Default")
      (node (ref "U7A") (pin "6") (pinfunction "GPOUT2_6") (pintype "bidirectional"))
    )
    (net (code "74") (name "unconnected-(U7A-GPOUT3-Pad7)") (class "Default")
      (node (ref "U7A") (pin "7") (pinfunction "GPOUT3_7") (pintype "bidirectional"))
    )
    (net (code "75") (name "unconnected-(U7A-GPOUT4-Pad8)") (class "Default")
      (node (ref "U7A") (pin "8") (pinfunction "GPOUT4_8") (pintype "bidirectional"))
    )
    (net (code "76") (name "unconnected-(U7A-GPOUT5-Pad9)") (class "Default")
      (node (ref "U7A") (pin "9") (pinfunction "GPOUT5_9") (pintype "bidirectional"))
    )
    (net (code "77") (name "unconnected-(U7A-GPOUT6-Pad10)") (class "Default")
      (node (ref "U7A") (pin "10") (pinfunction "GPOUT6_10") (pintype "bidirectional"))
    )
    (net (code "78") (name "unconnected-(U7A-GPOUT7-Pad11)") (class "Default")
      (node (ref "U7A") (pin "11") (pinfunction "GPOUT7_11") (pintype "bidirectional"))
    )
  )
)
